# one_key_usb_top.net
KiCad netlist of a schematic drawn in EAGLE
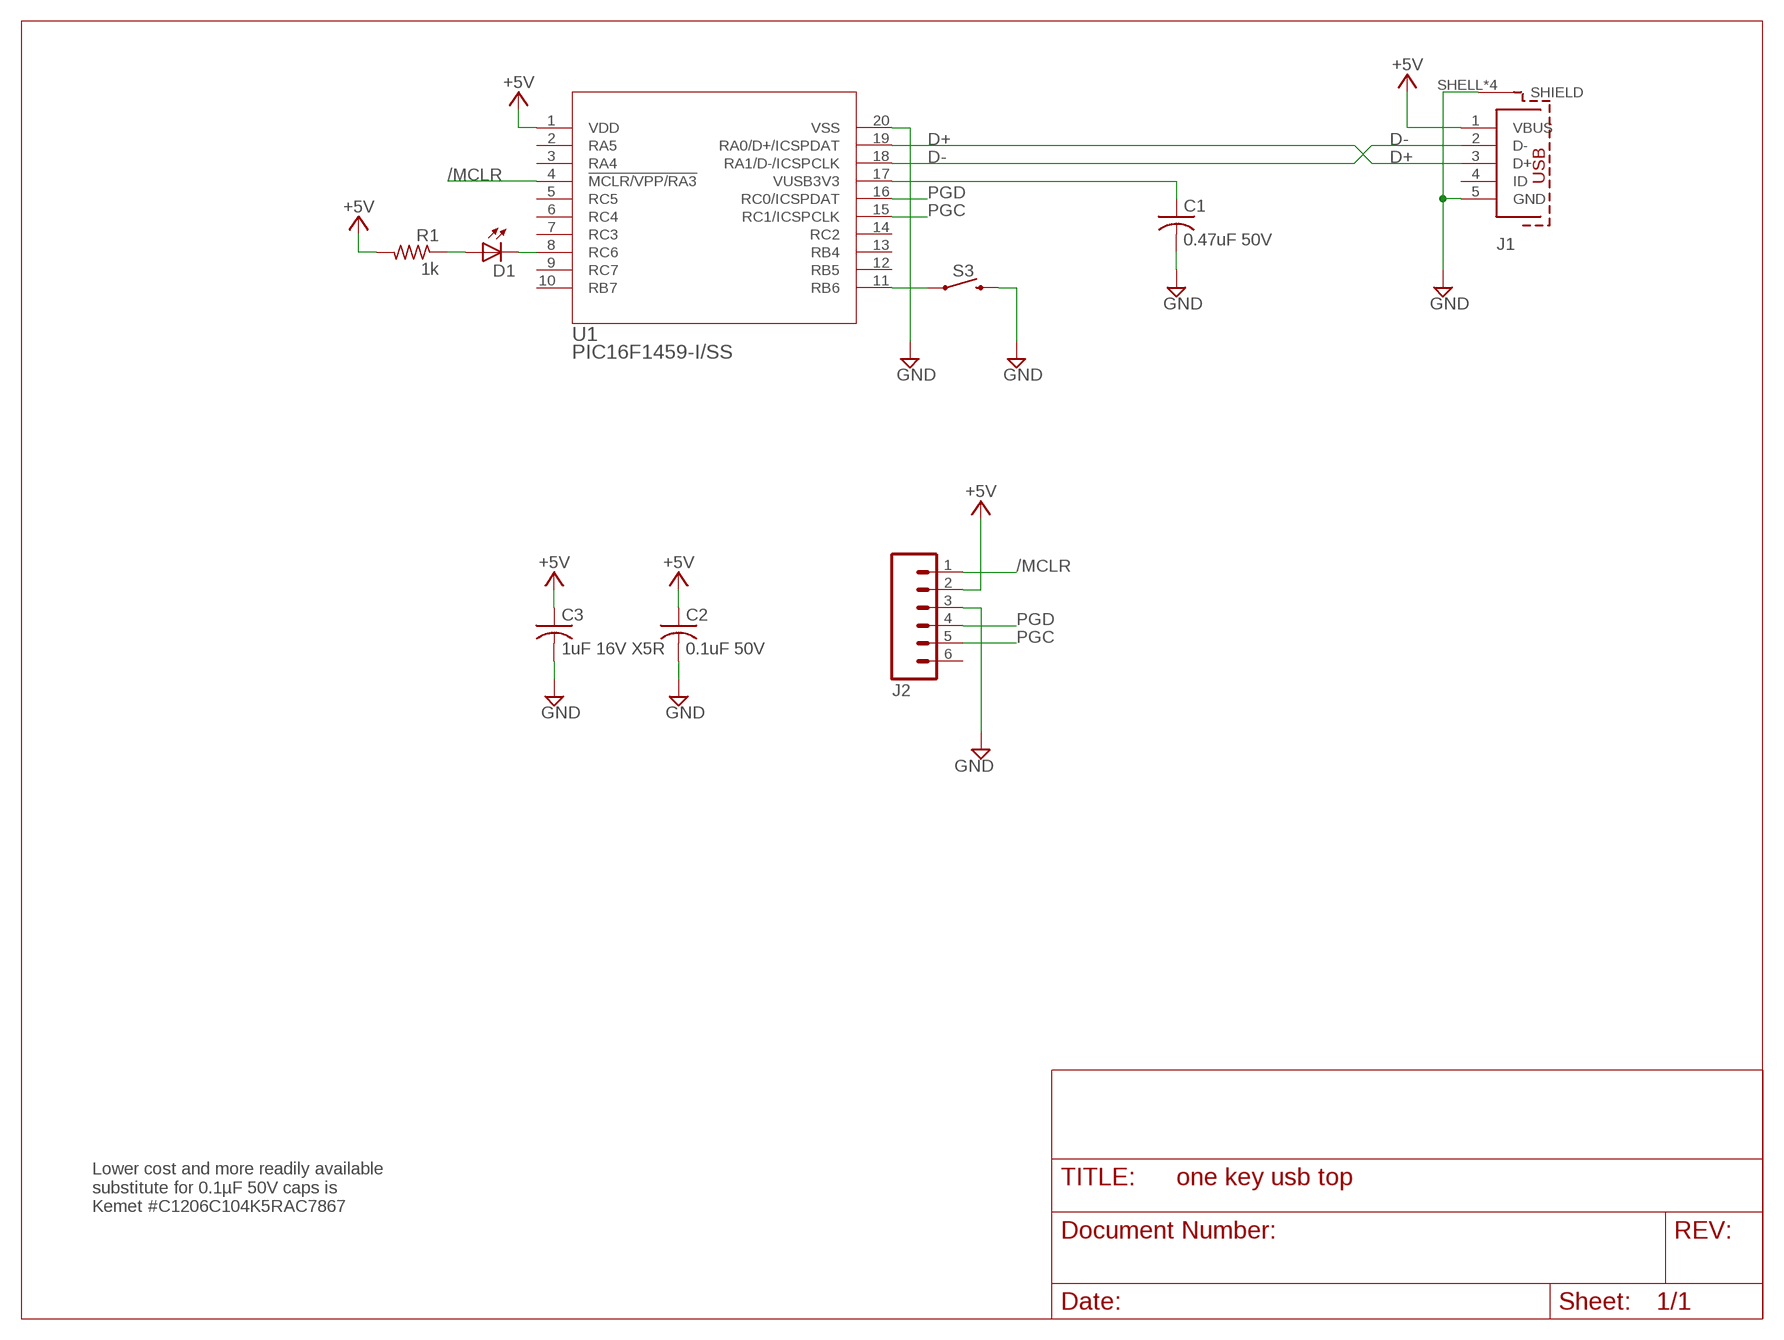
[diagram p0: schematic, sheet 1]

(export (version "E")
  (design (tool "Eeschema 10.0.6"))
  (components
    (comp (ref "C1")
      (value "0.47uF 50V")
      (footprint "eagle-import:C1206K")
      (fields (field (name "MFR") "KEMET") (field (name "MFR_PART_NO") "C1206C474K5RACTU"))
      (libsource (lib "eagle-import") (part "C-USC1206K"))
    )
    (comp (ref "C2")
      (value "0.1uF 50V")
      (footprint "eagle-import:C1206K")
      (fields (field (name "MFR") "KEMET") (field (name "MFR_PART_NO") "C1206S104M5RACTU"))
      (libsource (lib "eagle-import") (part "C-USC1206K"))
    )
    (comp (ref "C3")
      (value "1uF 16V X5R")
      (footprint "eagle-import:C1210")
      (fields (field (name "MFR") "KEMET") (field (name "MFR_PART_NO") "C1210C105K4PACTU"))
      (libsource (lib "eagle-import") (part "C-USC1210"))
    )
    (comp (ref "D1")
      (value "LEDKA-3528ASYC")
      (footprint "eagle-import:KA-3528ASYC")
      (libsource (lib "eagle-import") (part "LEDKA-3528ASYC"))
    )
    (comp (ref "J1")
      (value "629105136821")
      (footprint "eagle-import:629105136821")
      (libsource (lib "eagle-import") (part "629105136821"))
    )
    (comp (ref "J2")
      (value "M06SIP")
      (footprint "eagle-import:1X06")
      (libsource (lib "eagle-import") (part "M06SIP"))
    )
    (comp (ref "R1")
      (value "1k")
      (footprint "eagle-import:R1206")
      (fields (field (name "MFR") "BOURNS") (field (name "MFR_PART_NO") "CR1206-JW-102ELF"))
      (libsource (lib "eagle-import") (part "R-US_R1206"))
    )
    (comp (ref "S3")
      (value "MOMENTARY-SWITCH-SPST")
      (footprint "eagle-import:CHERRY-MX-NOLED")
      (libsource (lib "eagle-import") (part "MOMENTARY-SWITCH-SPST"))
    )
    (comp (ref "U1")
      (value "PIC16F1459-I/SS")
      (footprint "eagle-import:SSOP20_MC")
      (fields (field (name "MANUFACTURER_PART_NUMBER") "PIC16F1459ISS"))
      (libsource (lib "eagle-import") (part "PIC16F1459-I/SS"))
    )
  )
  (nets
    (net (code "1") (name "+5V") (class "Default")
      (node (ref "C2") (pin "1") (pinfunction "1_1") (pintype "passive"))
      (node (ref "C3") (pin "1") (pinfunction "1_1") (pintype "passive"))
      (node (ref "J1") (pin "1") (pinfunction "VBUS_1") (pintype "passive"))
      (node (ref "J2") (pin "2") (pinfunction "2_2") (pintype "passive"))
      (node (ref "R1") (pin "2") (pinfunction "2_2") (pintype "passive"))
      (node (ref "U1") (pin "1") (pinfunction "VDD_1") (pintype "power_in"))
    )
    (net (code "2") (name "/D+") (class "Default")
      (node (ref "J1") (pin "3") (pinfunction "D+_3") (pintype "passive"))
      (node (ref "U1") (pin "19") (pinfunction "RA0/D+/ICSPDAT_19") (pintype "bidirectional"))
    )
    (net (code "3") (name "/D-") (class "Default")
      (node (ref "J1") (pin "2") (pinfunction "D-_2") (pintype "passive"))
      (node (ref "U1") (pin "18") (pinfunction "RA1/D-/ICSPCLK_18") (pintype "bidirectional"))
    )
    (net (code "4") (name "/PGC") (class "Default")
      (node (ref "J2") (pin "5") (pinfunction "5_5") (pintype "passive"))
      (node (ref "U1") (pin "15") (pinfunction "RC1/ICSPCLK_15") (pintype "bidirectional"))
    )
    (net (code "5") (name "/PGD") (class "Default")
      (node (ref "J2") (pin "4") (pinfunction "4_4") (pintype "passive"))
      (node (ref "U1") (pin "16") (pinfunction "RC0/ICSPDAT_16") (pintype "bidirectional"))
    )
    (net (code "6") (name "/{slash}MCLR") (class "Default")
      (node (ref "J2") (pin "1") (pinfunction "1_1") (pintype "passive"))
      (node (ref "U1") (pin "4") (pinfunction "~{MCLR/VPP/RA3}_4") (pintype "bidirectional"))
    )
    (net (code "7") (name "GND") (class "Default")
      (node (ref "C1") (pin "2") (pinfunction "2_2") (pintype "passive"))
      (node (ref "C2") (pin "2") (pinfunction "2_2") (pintype "passive"))
      (node (ref "C3") (pin "2") (pinfunction "2_2") (pintype "passive"))
      (node (ref "J1") (pin "5") (pinfunction "GND_5") (pintype "passive"))
      (node (ref "J1") (pin "SHELL") (pinfunction "SHIELD_SHELL") (pintype "passive"))
      (node (ref "J1") (pin "SHELL1") (pinfunction "SHIELD_SHELL1") (pintype "passive"))
      (node (ref "J1") (pin "SHELL2") (pinfunction "SHIELD_SHELL2") (pintype "passive"))
      (node (ref "J1") (pin "SHELL3") (pinfunction "SHIELD_SHELL3") (pintype "passive"))
      (node (ref "J2") (pin "3") (pinfunction "3_3") (pintype "passive"))
      (node (ref "S3") (pin "S2") (pinfunction "2_S2") (pintype "passive"))
      (node (ref "U1") (pin "20") (pinfunction "VSS_20") (pintype "power_in"))
    )
    (net (code "8") (name "Net-(D1-PadA)") (class "Default")
      (node (ref "D1") (pin "A") (pinfunction "A_A") (pintype "passive"))
      (node (ref "R1") (pin "1") (pinfunction "1_1") (pintype "passive"))
    )
    (net (code "9") (name "Net-(S3-1)") (class "Default")
      (node (ref "S3") (pin "S1") (pinfunction "1_S1") (pintype "passive"))
      (node (ref "U1") (pin "11") (pinfunction "RB6_11") (pintype "bidirectional"))
    )
    (net (code "10") (name "Net-(U1-RC6)") (class "Default")
      (node (ref "D1") (pin "C") (pinfunction "C_C") (pintype "passive"))
      (node (ref "U1") (pin "8") (pinfunction "RC6_8") (pintype "bidirectional"))
    )
    (net (code "11") (name "Net-(U1-VUSB3V3)") (class "Default")
      (node (ref "C1") (pin "1") (pinfunction "1_1") (pintype "passive"))
      (node (ref "U1") (pin "17") (pinfunction "VUSB3V3_17") (pintype "power_in"))
    )
    (net (code "12") (name "unconnected-(J1-ID-Pad4)") (class "Default")
      (node (ref "J1") (pin "4") (pinfunction "ID_4") (pintype "passive"))
    )
    (net (code "13") (name "unconnected-(J2-Pad6)") (class "Default")
      (node (ref "J2") (pin "6") (pinfunction "6_6") (pintype "passive"))
    )
    (net (code "14") (name "unconnected-(U1-RA4-Pad3)") (class "Default")
      (node (ref "U1") (pin "3") (pinfunction "RA4_3") (pintype "bidirectional"))
    )
    (net (code "15") (name "unconnected-(U1-RA5-Pad2)") (class "Default")
      (node (ref "U1") (pin "2") (pinfunction "RA5_2") (pintype "bidirectional"))
    )
    (net (code "16") (name "unconnected-(U1-RB4-Pad13)") (class "Default")
      (node (ref "U1") (pin "13") (pinfunction "RB4_13") (pintype "bidirectional"))
    )
    (net (code "17") (name "unconnected-(U1-RB5-Pad12)") (class "Default")
      (node (ref "U1") (pin "12") (pinfunction "RB5_12") (pintype "bidirectional"))
    )
    (net (code "18") (name "unconnected-(U1-RB7-Pad10)") (class "Default")
      (node (ref "U1") (pin "10") (pinfunction "RB7_10") (pintype "bidirectional"))
    )
    (net (code "19") (name "unconnected-(U1-RC2-Pad14)") (class "Default")
      (node (ref "U1") (pin "14") (pinfunction "RC2_14") (pintype "bidirectional"))
    )
    (net (code "20") (name "unconnected-(U1-RC3-Pad7)") (class "Default")
      (node (ref "U1") (pin "7") (pinfunction "RC3_7") (pintype "bidirectional"))
    )
    (net (code "21") (name "unconnected-(U1-RC4-Pad6)") (class "Default")
      (node (ref "U1") (pin "6") (pinfunction "RC4_6") (pintype "bidirectional"))
    )
    (net (code "22") (name "unconnected-(U1-RC5-Pad5)") (class "Default")
      (node (ref "U1") (pin "5") (pinfunction "RC5_5") (pintype "bidirectional"))
    )
    (net (code "23") (name "unconnected-(U1-RC7-Pad9)") (class "Default")
      (node (ref "U1") (pin "9") (pinfunction "RC7_9") (pintype "bidirectional"))
    )
  )
)
